# ProPrj_X-Link_V9_3_M_2024-10-04.net
KiCad netlist of a schematic drawn in EasyEDA Pro
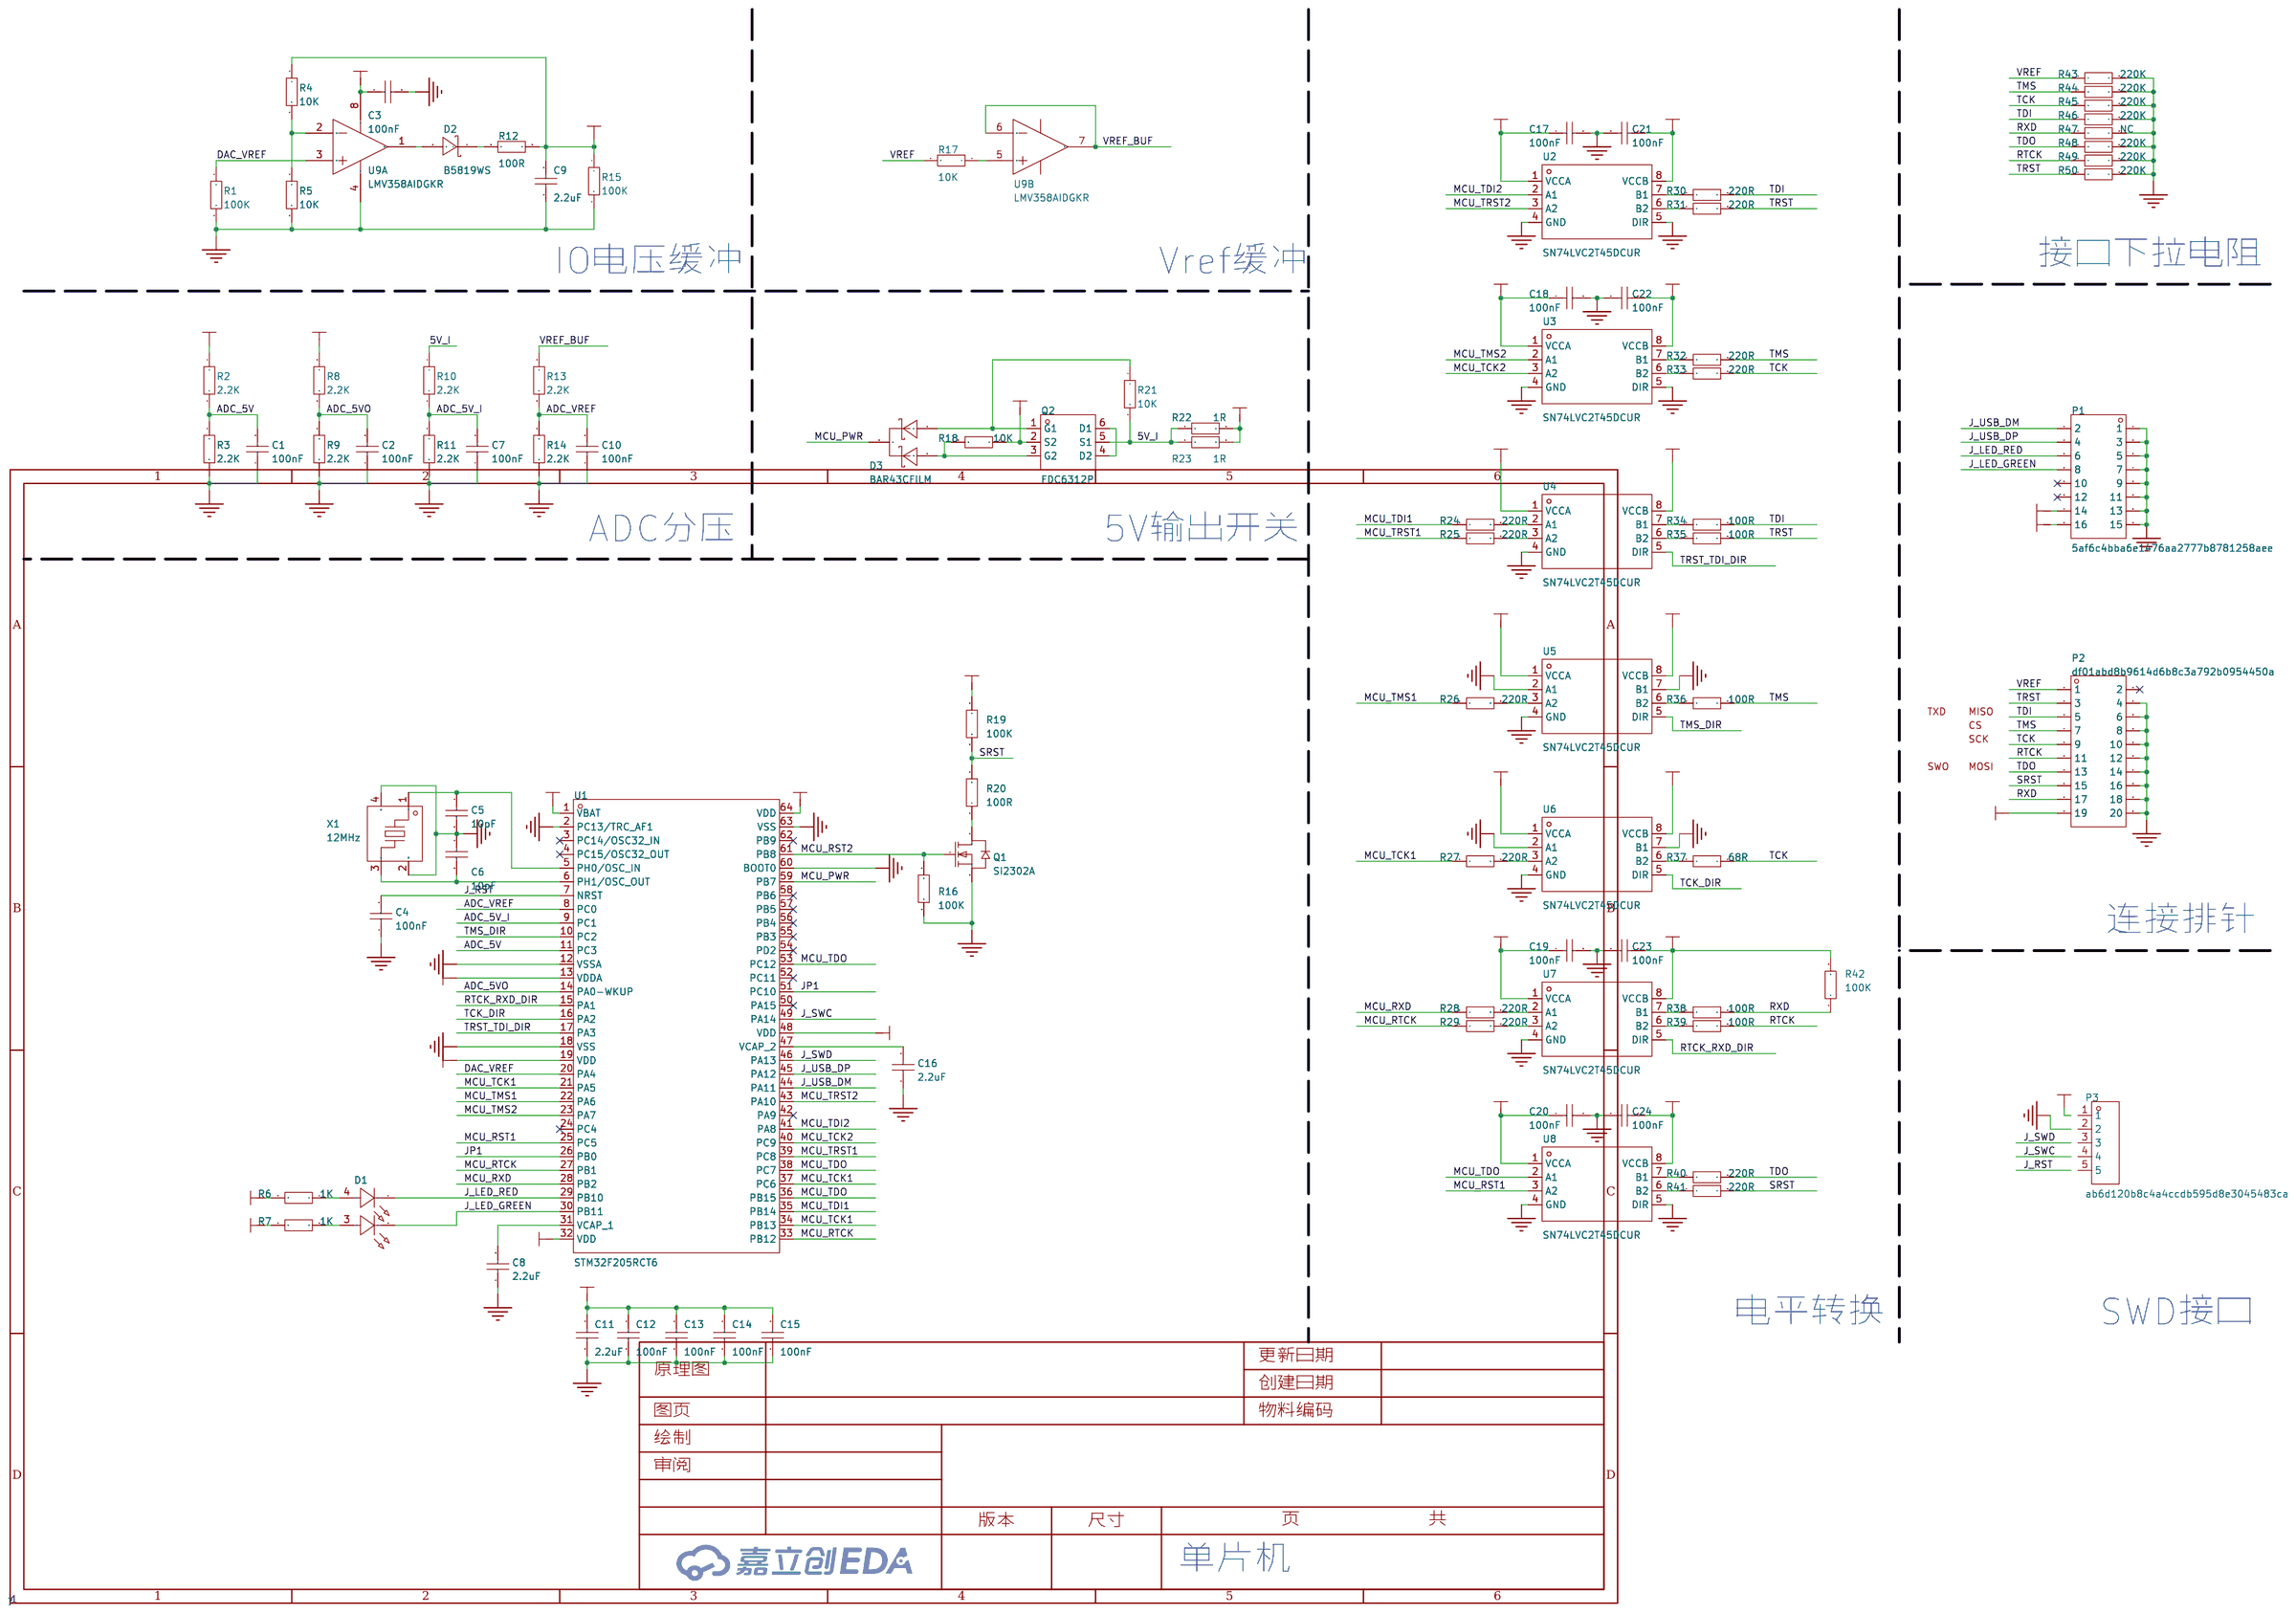
[diagram p0: schematic sheet]

(export (version "E")
  (design (tool "Eeschema 10.0.6"))
  (components
    (comp (ref "C1")
      (value "100nF")
      (footprint "easyedapro:C0402")
      (libsource (lib "easyedapro") (part "C0402"))
    )
    (comp (ref "C2")
      (value "100nF")
      (footprint "easyedapro:C0402")
      (libsource (lib "easyedapro") (part "C0402"))
    )
    (comp (ref "C3")
      (value "100nF")
      (footprint "easyedapro:C0402")
      (libsource (lib "easyedapro") (part "C0402"))
    )
    (comp (ref "C4")
      (value "100nF")
      (footprint "easyedapro:C0603")
      (libsource (lib "easyedapro") (part "C0603"))
    )
    (comp (ref "C5")
      (value "10pF")
      (footprint "easyedapro:C0402")
      (libsource (lib "easyedapro") (part "C0402"))
    )
    (comp (ref "C6")
      (value "10pF")
      (footprint "easyedapro:C0402")
      (libsource (lib "easyedapro") (part "C0402"))
    )
    (comp (ref "C7")
      (value "100nF")
      (footprint "easyedapro:C0402")
      (libsource (lib "easyedapro") (part "C0402"))
    )
    (comp (ref "C8")
      (value "2.2uF")
      (footprint "easyedapro:C0603")
      (libsource (lib "easyedapro") (part "C0603"))
    )
    (comp (ref "C9")
      (value "2.2uF")
      (footprint "easyedapro:C0402")
      (libsource (lib "easyedapro") (part "C0402"))
    )
    (comp (ref "C10")
      (value "100nF")
      (footprint "easyedapro:C0402")
      (libsource (lib "easyedapro") (part "C0402"))
    )
    (comp (ref "C11")
      (value "2.2uF")
      (footprint "easyedapro:C0603")
      (libsource (lib "easyedapro") (part "C0603"))
    )
    (comp (ref "C12")
      (value "100nF")
      (footprint "easyedapro:C0603")
      (libsource (lib "easyedapro") (part "C0603"))
    )
    (comp (ref "C13")
      (value "100nF")
      (footprint "easyedapro:C0603")
      (libsource (lib "easyedapro") (part "C0603"))
    )
    (comp (ref "C14")
      (value "100nF")
      (footprint "easyedapro:C0603")
      (libsource (lib "easyedapro") (part "C0603"))
    )
    (comp (ref "C15")
      (value "100nF")
      (footprint "easyedapro:C0603")
      (libsource (lib "easyedapro") (part "C0603"))
    )
    (comp (ref "C16")
      (value "2.2uF")
      (footprint "easyedapro:C0603")
      (libsource (lib "easyedapro") (part "C0603"))
    )
    (comp (ref "C17")
      (value "100nF")
      (footprint "easyedapro:C0603")
      (libsource (lib "easyedapro") (part "C0603"))
    )
    (comp (ref "C18")
      (value "100nF")
      (footprint "easyedapro:C0603")
      (libsource (lib "easyedapro") (part "C0603"))
    )
    (comp (ref "C19")
      (value "100nF")
      (footprint "easyedapro:C0603")
      (libsource (lib "easyedapro") (part "C0603"))
    )
    (comp (ref "C20")
      (value "100nF")
      (footprint "easyedapro:C0603")
      (libsource (lib "easyedapro") (part "C0603"))
    )
    (comp (ref "C21")
      (value "100nF")
      (footprint "easyedapro:C0603")
      (libsource (lib "easyedapro") (part "C0603"))
    )
    (comp (ref "C22")
      (value "100nF")
      (footprint "easyedapro:C0603")
      (libsource (lib "easyedapro") (part "C0603"))
    )
    (comp (ref "C23")
      (value "100nF")
      (footprint "easyedapro:C0603")
      (libsource (lib "easyedapro") (part "C0603"))
    )
    (comp (ref "C24")
      (value "100nF")
      (footprint "easyedapro:C0603")
      (libsource (lib "easyedapro") (part "C0603"))
    )
    (comp (ref "D1")
      (value "~")
      (footprint "easyedapro:LED1615")
      (libsource (lib "easyedapro") (part "LED1615"))
    )
    (comp (ref "D2")
      (value "B5819WS")
      (footprint "easyedapro:SOD-323_L1.8-W1.3-LS2.5-RD")
      (description "正向压降(Vf):600mV@1A;直流反向耐压(Vr):40V;平均整流电流(Io):1A;")
      (fields (field (name "Manufacturer") "CJ(江苏长电/长晶)"))
      (libsource (lib "easyedapro") (part "B5819WS_C22624"))
    )
    (comp (ref "D3")
      (value "BAR43CFILM")
      (footprint "easyedapro:SOT-23-3_L2.9-W1.3-P1.90-LS2.4-BR")
      (description "二极管配置:1对共阴极;正向压降(Vf):1V@100mA;直流反向耐压(Vr):30V;平均整流电流(Io):100mA;")
      (fields (field (name "Manufacturer") "ST(意法半导体)"))
      (libsource (lib "easyedapro") (part "BAR43CFILM"))
    )
    (comp (ref "P1")
      (value "5af6c4bba6e1476aa2777b8781258aee")
      (footprint "easyedapro:HDR-TH_16P-P1.27-V-M-R2-C8-S1.27-1")
      (libsource (lib "easyedapro") (part "HDR2x8_1.27"))
    )
    (comp (ref "P2")
      (value "df01abd8b9614d6b8c3a792b0954450a")
      (footprint "easyedapro:HDR-TH_20P-P1.27-V-M-R2-C10-S1.27")
      (libsource (lib "easyedapro") (part "HDR2x10_1.27"))
    )
    (comp (ref "P3")
      (value "ab6d120b8c4a4ccdb595d8e3045483ca")
      (footprint "easyedapro:HDR-TH_5P-P1.27-V-M")
      (libsource (lib "easyedapro") (part "HDR1x5_1.27"))
    )
    (comp (ref "Q1")
      (value "SI2302A")
      (footprint "easyedapro:SOT-23-3_L2.9-W1.3-P1.90-LS2.4-BR")
      (fields (field (name "Manufacturer") "UMW(友台半导体)"))
      (libsource (lib "easyedapro") (part "SI2302A"))
    )
    (comp (ref "Q2")
      (value "FDC6312P")
      (footprint "easyedapro:SOT-23-6_L2.9-W1.6-P0.95-LS2.8-BR")
      (description "类型:-;漏源电压(Vdss):-;连续漏极电流(Id):-;功率(Pd):-;导通电阻(RDS(on)@Vgs,Id):-;阈值电压(Vgs(th)@Id):-;")
      (fields (field (name "Manufacturer") "onsemi(安森美)"))
      (libsource (lib "easyedapro") (part "FDC6312P_C241767"))
    )
    (comp (ref "R1")
      (value "100K")
      (footprint "easyedapro:R0402")
      (libsource (lib "easyedapro") (part "R0402"))
    )
    (comp (ref "R2")
      (value "2.2K")
      (footprint "easyedapro:R0402")
      (libsource (lib "easyedapro") (part "R0402"))
    )
    (comp (ref "R3")
      (value "2.2K")
      (footprint "easyedapro:R0402")
      (libsource (lib "easyedapro") (part "R0402"))
    )
    (comp (ref "R4")
      (value "10K")
      (footprint "easyedapro:R0402")
      (libsource (lib "easyedapro") (part "R0402"))
    )
    (comp (ref "R5")
      (value "10K")
      (footprint "easyedapro:R0402")
      (libsource (lib "easyedapro") (part "R0402"))
    )
    (comp (ref "R6") (value "1K") (footprint "easyedapro:R0603") (libsource (lib "easyedapro") (part "电阻")))
    (comp (ref "R7") (value "1K") (footprint "easyedapro:R0603") (libsource (lib "easyedapro") (part "电阻")))
    (comp (ref "R8")
      (value "2.2K")
      (footprint "easyedapro:R0402")
      (libsource (lib "easyedapro") (part "R0402"))
    )
    (comp (ref "R9")
      (value "2.2K")
      (footprint "easyedapro:R0402")
      (libsource (lib "easyedapro") (part "R0402"))
    )
    (comp (ref "R10")
      (value "2.2K")
      (footprint "easyedapro:R0402")
      (libsource (lib "easyedapro") (part "R0402"))
    )
    (comp (ref "R11")
      (value "2.2K")
      (footprint "easyedapro:R0402")
      (libsource (lib "easyedapro") (part "R0402"))
    )
    (comp (ref "R12")
      (value "100R")
      (footprint "easyedapro:R0402")
      (libsource (lib "easyedapro") (part "R0402"))
    )
    (comp (ref "R13")
      (value "2.2K")
      (footprint "easyedapro:R0402")
      (libsource (lib "easyedapro") (part "R0402"))
    )
    (comp (ref "R14")
      (value "2.2K")
      (footprint "easyedapro:R0402")
      (libsource (lib "easyedapro") (part "R0402"))
    )
    (comp (ref "R15")
      (value "100K")
      (footprint "easyedapro:R0402")
      (libsource (lib "easyedapro") (part "R0402"))
    )
    (comp (ref "R16")
      (value "100K")
      (footprint "easyedapro:R0603")
      (libsource (lib "easyedapro") (part "电阻"))
    )
    (comp (ref "R17")
      (value "10K")
      (footprint "easyedapro:R0402")
      (libsource (lib "easyedapro") (part "R0402"))
    )
    (comp (ref "R18") (value "10K") (footprint "easyedapro:R0603") (libsource (lib "easyedapro") (part "电阻")))
    (comp (ref "R19")
      (value "100K")
      (footprint "easyedapro:R0603")
      (libsource (lib "easyedapro") (part "电阻"))
    )
    (comp (ref "R20")
      (value "100R")
      (footprint "easyedapro:R0603")
      (libsource (lib "easyedapro") (part "电阻"))
    )
    (comp (ref "R21") (value "10K") (footprint "easyedapro:R0603") (libsource (lib "easyedapro") (part "电阻")))
    (comp (ref "R22")
      (value "1R")
      (footprint "easyedapro:R0805")
      (libsource (lib "easyedapro") (part "R0805"))
    )
    (comp (ref "R23")
      (value "1R")
      (footprint "easyedapro:R0805")
      (libsource (lib "easyedapro") (part "R0805"))
    )
    (comp (ref "R24")
      (value "220R")
      (footprint "easyedapro:R0603")
      (libsource (lib "easyedapro") (part "电阻"))
    )
    (comp (ref "R25")
      (value "220R")
      (footprint "easyedapro:R0603")
      (libsource (lib "easyedapro") (part "电阻"))
    )
    (comp (ref "R26")
      (value "220R")
      (footprint "easyedapro:R0603")
      (libsource (lib "easyedapro") (part "电阻"))
    )
    (comp (ref "R27")
      (value "220R")
      (footprint "easyedapro:R0603")
      (libsource (lib "easyedapro") (part "电阻"))
    )
    (comp (ref "R28")
      (value "220R")
      (footprint "easyedapro:R0603")
      (libsource (lib "easyedapro") (part "电阻"))
    )
    (comp (ref "R29")
      (value "220R")
      (footprint "easyedapro:R0603")
      (libsource (lib "easyedapro") (part "电阻"))
    )
    (comp (ref "R30")
      (value "220R")
      (footprint "easyedapro:R0603")
      (libsource (lib "easyedapro") (part "电阻"))
    )
    (comp (ref "R31")
      (value "220R")
      (footprint "easyedapro:R0603")
      (libsource (lib "easyedapro") (part "电阻"))
    )
    (comp (ref "R32")
      (value "220R")
      (footprint "easyedapro:R0603")
      (libsource (lib "easyedapro") (part "电阻"))
    )
    (comp (ref "R33")
      (value "220R")
      (footprint "easyedapro:R0603")
      (libsource (lib "easyedapro") (part "电阻"))
    )
    (comp (ref "R34")
      (value "100R")
      (footprint "easyedapro:R0603")
      (libsource (lib "easyedapro") (part "电阻"))
    )
    (comp (ref "R35")
      (value "100R")
      (footprint "easyedapro:R0603")
      (libsource (lib "easyedapro") (part "电阻"))
    )
    (comp (ref "R36")
      (value "100R")
      (footprint "easyedapro:R0603")
      (libsource (lib "easyedapro") (part "电阻"))
    )
    (comp (ref "R37") (value "68R") (footprint "easyedapro:R0603") (libsource (lib "easyedapro") (part "电阻")))
    (comp (ref "R38")
      (value "100R")
      (footprint "easyedapro:R0603")
      (libsource (lib "easyedapro") (part "电阻"))
    )
    (comp (ref "R39")
      (value "100R")
      (footprint "easyedapro:R0603")
      (libsource (lib "easyedapro") (part "电阻"))
    )
    (comp (ref "R40")
      (value "220R")
      (footprint "easyedapro:R0603")
      (libsource (lib "easyedapro") (part "电阻"))
    )
    (comp (ref "R41")
      (value "220R")
      (footprint "easyedapro:R0603")
      (libsource (lib "easyedapro") (part "电阻"))
    )
    (comp (ref "R42")
      (value "100K")
      (footprint "easyedapro:R0603")
      (libsource (lib "easyedapro") (part "电阻"))
    )
    (comp (ref "R43")
      (value "220K")
      (footprint "easyedapro:R0603")
      (libsource (lib "easyedapro") (part "电阻"))
    )
    (comp (ref "R44")
      (value "220K")
      (footprint "easyedapro:R0603")
      (libsource (lib "easyedapro") (part "电阻"))
    )
    (comp (ref "R45")
      (value "220K")
      (footprint "easyedapro:R0603")
      (libsource (lib "easyedapro") (part "电阻"))
    )
    (comp (ref "R46")
      (value "220K")
      (footprint "easyedapro:R0603")
      (libsource (lib "easyedapro") (part "电阻"))
    )
    (comp (ref "R47") (value "NC") (footprint "easyedapro:R0603") (libsource (lib "easyedapro") (part "电阻")))
    (comp (ref "R48")
      (value "220K")
      (footprint "easyedapro:R0603")
      (libsource (lib "easyedapro") (part "电阻"))
    )
    (comp (ref "R49")
      (value "220K")
      (footprint "easyedapro:R0603")
      (libsource (lib "easyedapro") (part "电阻"))
    )
    (comp (ref "R50")
      (value "220K")
      (footprint "easyedapro:R0603")
      (libsource (lib "easyedapro") (part "电阻"))
    )
    (comp (ref "U1")
      (value "STM32F205RCT6")
      (footprint "easyedapro:LQFP-64_L10.0-W10.0-P0.50-LS12.0-BL")
      (description "CPU内核:CM3;程序存储容量:256KB;GPIO端口数量:51;工作电压范围:1.8V~3.6V;CPU最大主频:120MHz;")
      (fields (field (name "Manufacturer") "ST(意法半导体)"))
      (libsource (lib "easyedapro") (part "STM32F205RCT6"))
    )
    (comp (ref "U2")
      (value "SN74LVC2T45DCUR")
      (footprint "easyedapro:VSSOP-8_L2.4-W2.1-P0.50-LS3.2-BR")
      (description "SN74LVC2T45 具有可配置电压转换和三态输出的 2 位双电源总线收发器")
      (fields (field (name "Manufacturer") "TI(德州仪器)"))
      (libsource (lib "easyedapro") (part "SN74LVC2T45DCUR"))
    )
    (comp (ref "U3")
      (value "SN74LVC2T45DCUR")
      (footprint "easyedapro:VSSOP-8_L2.4-W2.1-P0.50-LS3.2-BR")
      (description "SN74LVC2T45 具有可配置电压转换和三态输出的 2 位双电源总线收发器")
      (fields (field (name "Manufacturer") "TI(德州仪器)"))
      (libsource (lib "easyedapro") (part "SN74LVC2T45DCUR"))
    )
    (comp (ref "U4")
      (value "SN74LVC2T45DCUR")
      (footprint "easyedapro:VSSOP-8_L2.4-W2.1-P0.50-LS3.2-BR")
      (description "SN74LVC2T45 具有可配置电压转换和三态输出的 2 位双电源总线收发器")
      (fields (field (name "Manufacturer") "TI(德州仪器)"))
      (libsource (lib "easyedapro") (part "SN74LVC2T45DCUR"))
    )
    (comp (ref "U5")
      (value "SN74LVC2T45DCUR")
      (footprint "easyedapro:VSSOP-8_L2.4-W2.1-P0.50-LS3.2-BR")
      (description "SN74LVC2T45 具有可配置电压转换和三态输出的 2 位双电源总线收发器")
      (fields (field (name "Manufacturer") "TI(德州仪器)"))
      (libsource (lib "easyedapro") (part "SN74LVC2T45DCUR"))
    )
    (comp (ref "U6")
      (value "SN74LVC2T45DCUR")
      (footprint "easyedapro:VSSOP-8_L2.4-W2.1-P0.50-LS3.2-BR")
      (description "SN74LVC2T45 具有可配置电压转换和三态输出的 2 位双电源总线收发器")
      (fields (field (name "Manufacturer") "TI(德州仪器)"))
      (libsource (lib "easyedapro") (part "SN74LVC2T45DCUR"))
    )
    (comp (ref "U7")
      (value "SN74LVC2T45DCUR")
      (footprint "easyedapro:VSSOP-8_L2.4-W2.1-P0.50-LS3.2-BR")
      (description "SN74LVC2T45 具有可配置电压转换和三态输出的 2 位双电源总线收发器")
      (fields (field (name "Manufacturer") "TI(德州仪器)"))
      (libsource (lib "easyedapro") (part "SN74LVC2T45DCUR"))
    )
    (comp (ref "U8")
      (value "SN74LVC2T45DCUR")
      (footprint "easyedapro:VSSOP-8_L2.4-W2.1-P0.50-LS3.2-BR")
      (description "SN74LVC2T45 具有可配置电压转换和三态输出的 2 位双电源总线收发器")
      (fields (field (name "Manufacturer") "TI(德州仪器)"))
      (libsource (lib "easyedapro") (part "SN74LVC2T45DCUR"))
    )
    (comp (ref "U9")
      (value "LMV358AIDGKR")
      (footprint "easyedapro:VSSOP-8_L3.0-W3.0-P0.65-LS5.0-BL")
      (description "放大器数:双路;增益带宽积(GBP):1MHz;输入偏置电流(Ib):10pA;压摆率(SR):1.7V/us;带宽(-3db):-;轨到轨:-;")
      (fields (field (name "Manufacturer") "TI(德州仪器)"))
      (libsource (lib "easyedapro") (part "LMV358AIDGKR"))
    )
    (comp (ref "X1")
      (value "12MHz")
      (footprint "easyedapro:CRYSTAL-SMD_4P-L3.2-W2.5-BL-A")
      (libsource (lib "easyedapro") (part "XTAL3225"))
    )
  )
  (nets
    (net (code "1") (name "/5V_I") (class "Default")
      (node (ref "Q2") (pin "5") (pinfunction "S1_5") (pintype "unspecified"))
      (node (ref "R10") (pin "1") (pinfunction "1_1") (pintype "input"))
      (node (ref "R21") (pin "2") (pinfunction "2_2") (pintype "input"))
      (node (ref "R22") (pin "1") (pinfunction "1_1") (pintype "input"))
      (node (ref "R23") (pin "1") (pinfunction "1_1") (pintype "input"))
    )
    (net (code "2") (name "/ADC_5V") (class "Default")
      (node (ref "C1") (pin "2") (pinfunction "2_2") (pintype "input"))
      (node (ref "R2") (pin "2") (pinfunction "2_2") (pintype "input"))
      (node (ref "R3") (pin "1") (pinfunction "1_1") (pintype "input"))
      (node (ref "U1") (pin "11") (pinfunction "PC3_11") (pintype "unspecified"))
    )
    (net (code "3") (name "/ADC_5VO") (class "Default")
      (node (ref "C2") (pin "2") (pinfunction "2_2") (pintype "input"))
      (node (ref "R8") (pin "2") (pinfunction "2_2") (pintype "input"))
      (node (ref "R9") (pin "1") (pinfunction "1_1") (pintype "input"))
      (node (ref "U1") (pin "14") (pinfunction "PA0-WKUP_14") (pintype "unspecified"))
    )
    (net (code "4") (name "/ADC_5V_I") (class "Default")
      (node (ref "C7") (pin "2") (pinfunction "2_2") (pintype "input"))
      (node (ref "R10") (pin "2") (pinfunction "2_2") (pintype "input"))
      (node (ref "R11") (pin "1") (pinfunction "1_1") (pintype "input"))
      (node (ref "U1") (pin "9") (pinfunction "PC1_9") (pintype "unspecified"))
    )
    (net (code "5") (name "/ADC_VREF") (class "Default")
      (node (ref "C10") (pin "2") (pinfunction "2_2") (pintype "input"))
      (node (ref "R13") (pin "2") (pinfunction "2_2") (pintype "input"))
      (node (ref "R14") (pin "1") (pinfunction "1_1") (pintype "input"))
      (node (ref "U1") (pin "8") (pinfunction "PC0_8") (pintype "unspecified"))
    )
    (net (code "6") (name "/DAC_VREF") (class "Default")
      (node (ref "R1") (pin "1") (pinfunction "1_1") (pintype "input"))
      (node (ref "U1") (pin "20") (pinfunction "PA4_20") (pintype "unspecified"))
      (node (ref "U9") (pin "3") (pinfunction "+INA_3") (pintype "unspecified"))
    )
    (net (code "7") (name "/JP1") (class "Default")
      (node (ref "U1") (pin "26") (pinfunction "PB0_26") (pintype "unspecified"))
      (node (ref "U1") (pin "51") (pinfunction "PC10_51") (pintype "unspecified"))
    )
    (net (code "8") (name "/J_LED_GREEN") (class "Default")
      (node (ref "D1") (pin "2") (pinfunction "K_2") (pintype "unspecified"))
      (node (ref "P1") (pin "8") (pinfunction "8_8") (pintype "unspecified"))
      (node (ref "U1") (pin "30") (pinfunction "PB11_30") (pintype "unspecified"))
    )
    (net (code "9") (name "/J_LED_RED") (class "Default")
      (node (ref "D1") (pin "1") (pinfunction "K_1") (pintype "unspecified"))
      (node (ref "P1") (pin "6") (pinfunction "6_6") (pintype "unspecified"))
      (node (ref "U1") (pin "29") (pinfunction "PB10_29") (pintype "unspecified"))
    )
    (net (code "10") (name "/J_RST") (class "Default")
      (node (ref "C4") (pin "2") (pinfunction "2_2") (pintype "input"))
      (node (ref "U1") (pin "7") (pinfunction "NRST_7") (pintype "unspecified"))
    )
    (net (code "11") (name "/J_SWC") (class "Default")
      (node (ref "U1") (pin "49") (pinfunction "PA14_49") (pintype "unspecified"))
    )
    (net (code "12") (name "/J_SWD") (class "Default")
      (node (ref "U1") (pin "46") (pinfunction "PA13_46") (pintype "unspecified"))
    )
    (net (code "13") (name "/J_USB_DM") (class "Default")
      (node (ref "P1") (pin "2") (pinfunction "2_2") (pintype "unspecified"))
      (node (ref "U1") (pin "44") (pinfunction "PA11_44") (pintype "unspecified"))
    )
    (net (code "14") (name "/J_USB_DP") (class "Default")
      (node (ref "P1") (pin "4") (pinfunction "4_4") (pintype "unspecified"))
      (node (ref "U1") (pin "45") (pinfunction "PA12_45") (pintype "unspecified"))
    )
    (net (code "15") (name "/MCU_PWR") (class "Default")
      (node (ref "D3") (pin "3") (pinfunction "K_3") (pintype "unspecified"))
      (node (ref "U1") (pin "59") (pinfunction "PB7_59") (pintype "unspecified"))
    )
    (net (code "16") (name "/MCU_RST1") (class "Default")
      (node (ref "U1") (pin "25") (pinfunction "PC5_25") (pintype "unspecified"))
      (node (ref "U8") (pin "3") (pinfunction "A2_3") (pintype "unspecified"))
    )
    (net (code "17") (name "/MCU_RST2") (class "Default")
      (node (ref "Q1") (pin "1") (pinfunction "G_1") (pintype "unspecified"))
      (node (ref "R16") (pin "1") (pinfunction "1_1") (pintype "input"))
      (node (ref "U1") (pin "61") (pinfunction "PB8_61") (pintype "unspecified"))
    )
    (net (code "18") (name "/MCU_RTCK") (class "Default")
      (node (ref "R29") (pin "1") (pinfunction "1_1") (pintype "input"))
      (node (ref "U1") (pin "27") (pinfunction "PB1_27") (pintype "unspecified"))
      (node (ref "U1") (pin "33") (pinfunction "PB12_33") (pintype "unspecified"))
    )
    (net (code "19") (name "/MCU_RXD") (class "Default")
      (node (ref "R28") (pin "1") (pinfunction "1_1") (pintype "input"))
      (node (ref "U1") (pin "28") (pinfunction "PB2_28") (pintype "unspecified"))
    )
    (net (code "20") (name "/MCU_TCK1") (class "Default")
      (node (ref "R27") (pin "1") (pinfunction "1_1") (pintype "input"))
      (node (ref "U1") (pin "21") (pinfunction "PA5_21") (pintype "unspecified"))
      (node (ref "U1") (pin "34") (pinfunction "PB13_34") (pintype "unspecified"))
      (node (ref "U1") (pin "37") (pinfunction "PC6_37") (pintype "unspecified"))
    )
    (net (code "21") (name "/MCU_TCK2") (class "Default")
      (node (ref "U1") (pin "40") (pinfunction "PC9_40") (pintype "unspecified"))
      (node (ref "U3") (pin "3") (pinfunction "A2_3") (pintype "unspecified"))
    )
    (net (code "22") (name "/MCU_TDI1") (class "Default")
      (node (ref "R24") (pin "1") (pinfunction "1_1") (pintype "input"))
      (node (ref "U1") (pin "35") (pinfunction "PB14_35") (pintype "unspecified"))
    )
    (net (code "23") (name "/MCU_TDI2") (class "Default")
      (node (ref "U1") (pin "41") (pinfunction "PA8_41") (pintype "unspecified"))
      (node (ref "U2") (pin "2") (pinfunction "A1_2") (pintype "unspecified"))
    )
    (net (code "24") (name "/MCU_TDO") (class "Default")
      (node (ref "U1") (pin "36") (pinfunction "PB15_36") (pintype "unspecified"))
      (node (ref "U1") (pin "38") (pinfunction "PC7_38") (pintype "unspecified"))
      (node (ref "U1") (pin "53") (pinfunction "PC12_53") (pintype "unspecified"))
      (node (ref "U8") (pin "2") (pinfunction "A1_2") (pintype "unspecified"))
    )
    (net (code "25") (name "/MCU_TMS1") (class "Default")
      (node (ref "R26") (pin "1") (pinfunction "1_1") (pintype "input"))
      (node (ref "U1") (pin "22") (pinfunction "PA6_22") (pintype "unspecified"))
    )
    (net (code "26") (name "/MCU_TMS2") (class "Default")
      (node (ref "U1") (pin "23") (pinfunction "PA7_23") (pintype "unspecified"))
      (node (ref "U3") (pin "2") (pinfunction "A1_2") (pintype "unspecified"))
    )
    (net (code "27") (name "/MCU_TRST1") (class "Default")
      (node (ref "R25") (pin "1") (pinfunction "1_1") (pintype "input"))
      (node (ref "U1") (pin "39") (pinfunction "PC8_39") (pintype "unspecified"))
    )
    (net (code "28") (name "/MCU_TRST2") (class "Default")
      (node (ref "U1") (pin "43") (pinfunction "PA10_43") (pintype "unspecified"))
      (node (ref "U2") (pin "3") (pinfunction "A2_3") (pintype "unspecified"))
    )
    (net (code "29") (name "/RTCK") (class "Default")
      (node (ref "P2") (pin "11") (pinfunction "11_11") (pintype "unspecified"))
      (node (ref "R39") (pin "2") (pinfunction "2_2") (pintype "input"))
      (node (ref "R49") (pin "1") (pinfunction "1_1") (pintype "input"))
    )
    (net (code "30") (name "/RTCK_RXD_DIR") (class "Default")
      (node (ref "U1") (pin "15") (pinfunction "PA1_15") (pintype "unspecified"))
      (node (ref "U7") (pin "5") (pinfunction "DIR_5") (pintype "unspecified"))
    )
    (net (code "31") (name "/RXD") (class "Default")
      (node (ref "P2") (pin "17") (pinfunction "17_17") (pintype "unspecified"))
      (node (ref "R38") (pin "2") (pinfunction "2_2") (pintype "input"))
      (node (ref "R42") (pin "1") (pinfunction "1_1") (pintype "input"))
      (node (ref "R47") (pin "1") (pinfunction "1_1") (pintype "input"))
    )
    (net (code "32") (name "/SRST") (class "Default")
      (node (ref "P2") (pin "15") (pinfunction "15_15") (pintype "unspecified"))
      (node (ref "R19") (pin "2") (pinfunction "2_2") (pintype "input"))
      (node (ref "R20") (pin "2") (pinfunction "2_2") (pintype "input"))
      (node (ref "R41") (pin "2") (pinfunction "2_2") (pintype "input"))
    )
    (net (code "33") (name "/TCK") (class "Default")
      (node (ref "P2") (pin "9") (pinfunction "9_9") (pintype "unspecified"))
      (node (ref "R33") (pin "2") (pinfunction "2_2") (pintype "input"))
      (node (ref "R37") (pin "2") (pinfunction "2_2") (pintype "input"))
      (node (ref "R45") (pin "1") (pinfunction "1_1") (pintype "input"))
    )
    (net (code "34") (name "/TCK_DIR") (class "Default")
      (node (ref "U1") (pin "16") (pinfunction "PA2_16") (pintype "unspecified"))
      (node (ref "U6") (pin "5") (pinfunction "DIR_5") (pintype "unspecified"))
    )
    (net (code "35") (name "/TDI") (class "Default")
      (node (ref "P2") (pin "5") (pinfunction "5_5") (pintype "unspecified"))
      (node (ref "R30") (pin "2") (pinfunction "2_2") (pintype "input"))
      (node (ref "R34") (pin "2") (pinfunction "2_2") (pintype "input"))
      (node (ref "R46") (pin "1") (pinfunction "1_1") (pintype "input"))
    )
    (net (code "36") (name "/TDO") (class "Default")
      (node (ref "P2") (pin "13") (pinfunction "13_13") (pintype "unspecified"))
      (node (ref "R40") (pin "2") (pinfunction "2_2") (pintype "input"))
      (node (ref "R48") (pin "1") (pinfunction "1_1") (pintype "input"))
    )
    (net (code "37") (name "/TMS") (class "Default")
      (node (ref "P2") (pin "7") (pinfunction "7_7") (pintype "unspecified"))
      (node (ref "R32") (pin "2") (pinfunction "2_2") (pintype "input"))
      (node (ref "R36") (pin "2") (pinfunction "2_2") (pintype "input"))
      (node (ref "R44") (pin "1") (pinfunction "1_1") (pintype "input"))
    )
    (net (code "38") (name "/TMS_DIR") (class "Default")
      (node (ref "U1") (pin "10") (pinfunction "PC2_10") (pintype "unspecified"))
      (node (ref "U5") (pin "5") (pinfunction "DIR_5") (pintype "unspecified"))
    )
    (net (code "39") (name "/TRST") (class "Default")
      (node (ref "P2") (pin "3") (pinfunction "3_3") (pintype "unspecified"))
      (node (ref "R31") (pin "2") (pinfunction "2_2") (pintype "input"))
      (node (ref "R35") (pin "2") (pinfunction "2_2") (pintype "input"))
      (node (ref "R50") (pin "1") (pinfunction "1_1") (pintype "input"))
    )
    (net (code "40") (name "/TRST_TDI_DIR") (class "Default")
      (node (ref "U1") (pin "17") (pinfunction "PA3_17") (pintype "unspecified"))
      (node (ref "U4") (pin "5") (pinfunction "DIR_5") (pintype "unspecified"))
    )
    (net (code "41") (name "/VREF") (class "Default")
      (node (ref "P2") (pin "1") (pinfunction "1_1") (pintype "unspecified"))
      (node (ref "R17") (pin "2") (pinfunction "2_2") (pintype "input"))
      (node (ref "R43") (pin "1") (pinfunction "1_1") (pintype "input"))
    )
    (net (code "42") (name "/VREF_BUF") (class "Default")
      (node (ref "R13") (pin "1") (pinfunction "1_1") (pintype "input"))
      (node (ref "U9") (pin "6") (pinfunction "-INB_6") (pintype "unspecified"))
      (node (ref "U9") (pin "7") (pinfunction "OUTB_7") (pintype "output"))
    )
    (net (code "43") (name "3.3V") (class "Default")
      (node (ref "C11") (pin "2") (pinfunction "2_2") (pintype "input"))
      (node (ref "C12") (pin "2") (pinfunction "2_2") (pintype "input"))
      (node (ref "C13") (pin "2") (pinfunction "2_2") (pintype "input"))
      (node (ref "C14") (pin "2") (pinfunction "2_2") (pintype "input"))
      (node (ref "C15") (pin "2") (pinfunction "2_2") (pintype "input"))
      (node (ref "C17") (pin "1") (pinfunction "1_1") (pintype "input"))
      (node (ref "C18") (pin "1") (pinfunction "1_1") (pintype "input"))
      (node (ref "C19") (pin "1") (pinfunction "1_1") (pintype "input"))
      (node (ref "C20") (pin "1") (pinfunction "1_1") (pintype "input"))
      (node (ref "P1") (pin "14") (pinfunction "14_14") (pintype "unspecified"))
      (node (ref "R6") (pin "2") (pinfunction "2_2") (pintype "input"))
      (node (ref "R7") (pin "2") (pinfunction "2_2") (pintype "input"))
      (node (ref "U1") (pin "1") (pinfunction "VBAT_1") (pintype "unspecified"))
      (node (ref "U1") (pin "13") (pinfunction "VDDA_13") (pintype "unspecified"))
      (node (ref "U1") (pin "19") (pinfunction "VDD_19") (pintype "unspecified"))
      (node (ref "U1") (pin "32") (pinfunction "VDD_32") (pintype "unspecified"))
      (node (ref "U1") (pin "48") (pinfunction "VDD_48") (pintype "unspecified"))
      (node (ref "U1") (pin "64") (pinfunction "VDD_64") (pintype "unspecified"))
      (node (ref "U2") (pin "1") (pinfunction "VCCA_1") (pintype "unspecified"))
      (node (ref "U3") (pin "1") (pinfunction "VCCA_1") (pintype "unspecified"))
      (node (ref "U4") (pin "1") (pinfunction "VCCA_1") (pintype "unspecified"))
      (node (ref "U5") (pin "1") (pinfunction "VCCA_1") (pintype "unspecified"))
      (node (ref "U6") (pin "1") (pinfunction "VCCA_1") (pintype "unspecified"))
      (node (ref "U7") (pin "1") (pinfunction "VCCA_1") (pintype "unspecified"))
      (node (ref "U8") (pin "1") (pinfunction "VCCA_1") (pintype "unspecified"))
    )
    (net (code "44") (name "5V") (class "Default")
      (node (ref "C3") (pin "1") (pinfunction "1_1") (pintype "input"))
      (node (ref "P1") (pin "16") (pinfunction "16_16") (pintype "unspecified"))
      (node (ref "R2") (pin "1") (pinfunction "1_1") (pintype "input"))
      (node (ref "R22") (pin "2") (pinfunction "2_2") (pintype "input"))
      (node (ref "R23") (pin "2") (pinfunction "2_2") (pintype "input"))
      (node (ref "U9") (pin "8") (pinfunction "V+_8") (pintype "unspecified"))
    )
    (net (code "45") (name "5V_OUT") (class "Default")
      (node (ref "P2") (pin "19") (pinfunction "19_19") (pintype "unspecified"))
      (node (ref "Q2") (pin "2") (pinfunction "S2_2") (pintype "unspecified"))
      (node (ref "R18") (pin "1") (pinfunction "1_1") (pintype "input"))
      (node (ref "R8") (pin "1") (pinfunction "1_1") (pintype "input"))
    )
    (net (code "46") (name "GND") (class "Default")
      (node (ref "C1") (pin "1") (pinfunction "1_1") (pintype "input"))
      (node (ref "C10") (pin "1") (pinfunction "1_1") (pintype "input"))
      (node (ref "C11") (pin "1") (pinfunction "1_1") (pintype "input"))
      (node (ref "C12") (pin "1") (pinfunction "1_1") (pintype "input"))
      (node (ref "C13") (pin "1") (pinfunction "1_1") (pintype "input"))
      (node (ref "C14") (pin "1") (pinfunction "1_1") (pintype "input"))
      (node (ref "C15") (pin "1") (pinfunction "1_1") (pintype "input"))
      (node (ref "C16") (pin "1") (pinfunction "1_1") (pintype "input"))
      (node (ref "C17") (pin "2") (pinfunction "2_2") (pintype "input"))
      (node (ref "C18") (pin "2") (pinfunction "2_2") (pintype "input"))
      (node (ref "C19") (pin "2") (pinfunction "2_2") (pintype "input"))
      (node (ref "C2") (pin "1") (pinfunction "1_1") (pintype "input"))
      (node (ref "C20") (pin "2") (pinfunction "2_2") (pintype "input"))
      (node (ref "C21") (pin "1") (pinfunction "1_1") (pintype "input"))
      (node (ref "C22") (pin "1") (pinfunction "1_1") (pintype "input"))
      (node (ref "C23") (pin "1") (pinfunction "1_1") (pintype "input"))
      (node (ref "C24") (pin "1") (pinfunction "1_1") (pintype "input"))
      (node (ref "C3") (pin "2") (pinfunction "2_2") (pintype "input"))
      (node (ref "C4") (pin "1") (pinfunction "1_1") (pintype "input"))
      (node (ref "C5") (pin "2") (pinfunction "2_2") (pintype "input"))
      (node (ref "C6") (pin "1") (pinfunction "1_1") (pintype "input"))
      (node (ref "C7") (pin "1") (pinfunction "1_1") (pintype "input"))
      (node (ref "C8") (pin "1") (pinfunction "1_1") (pintype "input"))
      (node (ref "C9") (pin "1") (pinfunction "1_1") (pintype "input"))
      (node (ref "P1") (pin "1") (pinfunction "1_1") (pintype "unspecified"))
      (node (ref "P1") (pin "11") (pinfunction "11_11") (pintype "unspecified"))
      (node (ref "P1") (pin "13") (pinfunction "13_13") (pintype "unspecified"))
      (node (ref "P1") (pin "15") (pinfunction "15_15") (pintype "unspecified"))
      (node (ref "P1") (pin "3") (pinfunction "3_3") (pintype "unspecified"))
      (node (ref "P1") (pin "5") (pinfunction "5_5") (pintype "unspecified"))
      (node (ref "P1") (pin "7") (pinfunction "7_7") (pintype "unspecified"))
      (node (ref "P1") (pin "9") (pinfunction "9_9") (pintype "unspecified"))
      (node (ref "P2") (pin "10") (pinfunction "10_10") (pintype "unspecified"))
      (node (ref "P2") (pin "12") (pinfunction "12_12") (pintype "unspecified"))
      (node (ref "P2") (pin "14") (pinfunction "14_14") (pintype "unspecified"))
      (node (ref "P2") (pin "16") (pinfunction "16_16") (pintype "unspecified"))
      (node (ref "P2") (pin "18") (pinfunction "18_18") (pintype "unspecified"))
      (node (ref "P2") (pin "20") (pinfunction "20_20") (pintype "unspecified"))
      (node (ref "P2") (pin "4") (pinfunction "4_4") (pintype "unspecified"))
      (node (ref "P2") (pin "6") (pinfunction "6_6") (pintype "unspecified"))
      (node (ref "P2") (pin "8") (pinfunction "8_8") (pintype "unspecified"))
      (node (ref "Q1") (pin "2") (pinfunction "S_2") (pintype "unspecified"))
      (node (ref "R1") (pin "2") (pinfunction "2_2") (pintype "input"))
      (node (ref "R11") (pin "2") (pinfunction "2_2") (pintype "input"))
      (node (ref "R14") (pin "2") (pinfunction "2_2") (pintype "input"))
      (node (ref "R15") (pin "2") (pinfunction "2_2") (pintype "input"))
      (node (ref "R16") (pin "2") (pinfunction "2_2") (pintype "input"))
      (node (ref "R3") (pin "2") (pinfunction "2_2") (pintype "input"))
      (node (ref "R43") (pin "2") (pinfunction "2_2") (pintype "input"))
      (node (ref "R44") (pin "2") (pinfunction "2_2") (pintype "input"))
      (node (ref "R45") (pin "2") (pinfunction "2_2") (pintype "input"))
      (node (ref "R46") (pin "2") (pinfunction "2_2") (pintype "input"))
      (node (ref "R47") (pin "2") (pinfunction "2_2") (pintype "input"))
      (node (ref "R48") (pin "2") (pinfunction "2_2") (pintype "input"))
      (node (ref "R49") (pin "2") (pinfunction "2_2") (pintype "input"))
      (node (ref "R5") (pin "2") (pinfunction "2_2") (pintype "input"))
      (node (ref "R50") (pin "2") (pinfunction "2_2") (pintype "input"))
      (node (ref "R9") (pin "2") (pinfunction "2_2") (pintype "input"))
      (node (ref "U1") (pin "12") (pinfunction "VSSA_12") (pintype "unspecified"))
      (node (ref "U1") (pin "18") (pinfunction "VSS_18") (pintype "unspecified"))
      (node (ref "U1") (pin "2") (pinfunction "PC13/TRC_AF1_2") (pintype "unspecified"))
      (node (ref "U1") (pin "60") (pinfunction "BOOT0_60") (pintype "unspecified"))
      (node (ref "U1") (pin "63") (pinfunction "VSS_63") (pintype "unspecified"))
      (node (ref "U2") (pin "4") (pinfunction "GND_4") (pintype "unspecified"))
      (node (ref "U2") (pin "5") (pinfunction "DIR_5") (pintype "unspecified"))
      (node (ref "U3") (pin "4") (pinfunction "GND_4") (pintype "unspecified"))
      (node (ref "U3") (pin "5") (pinfunction "DIR_5") (pintype "unspecified"))
      (node (ref "U4") (pin "4") (pinfunction "GND_4") (pintype "unspecified"))
      (node (ref "U5") (pin "2") (pinfunction "A1_2") (pintype "unspecified"))
      (node (ref "U5") (pin "4") (pinfunction "GND_4") (pintype "unspecified"))
      (node (ref "U5") (pin "7") (pinfunction "B1_7") (pintype "unspecified"))
      (node (ref "U6") (pin "2") (pinfunction "A1_2") (pintype "unspecified"))
      (node (ref "U6") (pin "4") (pinfunction "GND_4") (pintype "unspecified"))
      (node (ref "U6") (pin "7") (pinfunction "B1_7") (pintype "unspecified"))
      (node (ref "U7") (pin "4") (pinfunction "GND_4") (pintype "unspecified"))
      (node (ref "U8") (pin "4") (pinfunction "GND_4") (pintype "unspecified"))
      (node (ref "U8") (pin "5") (pinfunction "DIR_5") (pintype "unspecified"))
      (node (ref "U9") (pin "4") (pinfunction "V-_4") (pintype "unspecified"))
      (node (ref "X1") (pin "2") (pinfunction "GND_2") (pintype "input"))
      (node (ref "X1") (pin "4") (pinfunction "GND_4") (pintype "input"))
    )
    (net (code "47") (name "Net-(D1-A-Pad3)") (class "Default")
      (node (ref "D1") (pin "3") (pinfunction "A_3") (pintype "unspecified"))
      (node (ref "R7") (pin "1") (pinfunction "1_1") (pintype "input"))
    )
    (net (code "48") (name "Net-(D1-A-Pad4)") (class "Default")
      (node (ref "D1") (pin "4") (pinfunction "A_4") (pintype "unspecified"))
      (node (ref "R6") (pin "1") (pinfunction "1_1") (pintype "input"))
    )
    (net (code "49") (name "Net-(D2-A)") (class "Default")
      (node (ref "D2") (pin "2") (pinfunction "A_2") (pintype "unspecified"))
      (node (ref "U9") (pin "1") (pinfunction "OUTA_1") (pintype "output"))
    )
    (net (code "50") (name "Net-(D2-K)") (class "Default")
      (node (ref "D2") (pin "1") (pinfunction "K_1") (pintype "unspecified"))
      (node (ref "R12") (pin "2") (pinfunction "2_2") (pintype "input"))
    )
    (net (code "51") (name "Net-(D3-A1)") (class "Default")
      (node (ref "D3") (pin "1") (pinfunction "A1_1") (pintype "unspecified"))
      (node (ref "Q2") (pin "3") (pinfunction "G2_3") (pintype "unspecified"))
      (node (ref "R18") (pin "2") (pinfunction "2_2") (pintype "input"))
    )
    (net (code "52") (name "Net-(D3-A2)") (class "Default")
      (node (ref "D3") (pin "2") (pinfunction "A2_2") (pintype "unspecified"))
      (node (ref "Q2") (pin "1") (pinfunction "G1_1") (pintype "unspecified"))
      (node (ref "R21") (pin "1") (pinfunction "1_1") (pintype "input"))
    )
    (net (code "53") (name "Net-(Q1-D)") (class "Default")
      (node (ref "Q1") (pin "3") (pinfunction "D_3") (pintype "unspecified"))
      (node (ref "R20") (pin "1") (pinfunction "1_1") (pintype "input"))
    )
    (net (code "54") (name "Net-(Q2-D1)") (class "Default")
      (node (ref "Q2") (pin "4") (pinfunction "D2_4") (pintype "unspecified"))
      (node (ref "Q2") (pin "6") (pinfunction "D1_6") (pintype "unspecified"))
    )
    (net (code "55") (name "Net-(U1-PH0{slash}OSC_IN)") (class "Default")
      (node (ref "C5") (pin "1") (pinfunction "1_1") (pintype "input"))
      (node (ref "U1") (pin "5") (pinfunction "PH0/OSC_IN_5") (pintype "unspecified"))
      (node (ref "X1") (pin "1") (pinfunction "1_1") (pintype "input"))
    )
    (net (code "56") (name "Net-(U1-PH1{slash}OSC_OUT)") (class "Default")
      (node (ref "C6") (pin "2") (pinfunction "2_2") (pintype "input"))
      (node (ref "U1") (pin "6") (pinfunction "PH1/OSC_OUT_6") (pintype "unspecified"))
      (node (ref "X1") (pin "3") (pinfunction "3_3") (pintype "input"))
    )
    (net (code "57") (name "Net-(U1-VCAP_1)") (class "Default")
      (node (ref "C8") (pin "2") (pinfunction "2_2") (pintype "input"))
      (node (ref "U1") (pin "31") (pinfunction "VCAP_1_31") (pintype "unspecified"))
    )
    (net (code "58") (name "Net-(U1-VCAP_2)") (class "Default")
      (node (ref "C16") (pin "2") (pinfunction "2_2") (pintype "input"))
      (node (ref "U1") (pin "47") (pinfunction "VCAP_2_47") (pintype "unspecified"))
    )
    (net (code "59") (name "Net-(U2-B1)") (class "Default")
      (node (ref "R30") (pin "1") (pinfunction "1_1") (pintype "input"))
      (node (ref "U2") (pin "7") (pinfunction "B1_7") (pintype "unspecified"))
    )
    (net (code "60") (name "Net-(U2-B2)") (class "Default")
      (node (ref "R31") (pin "1") (pinfunction "1_1") (pintype "input"))
      (node (ref "U2") (pin "6") (pinfunction "B2_6") (pintype "unspecified"))
    )
    (net (code "61") (name "Net-(U3-B1)") (class "Default")
      (node (ref "R32") (pin "1") (pinfunction "1_1") (pintype "input"))
      (node (ref "U3") (pin "7") (pinfunction "B1_7") (pintype "unspecified"))
    )
    (net (code "62") (name "Net-(U3-B2)") (class "Default")
      (node (ref "R33") (pin "1") (pinfunction "1_1") (pintype "input"))
      (node (ref "U3") (pin "6") (pinfunction "B2_6") (pintype "unspecified"))
    )
    (net (code "63") (name "Net-(U4-A1)") (class "Default")
      (node (ref "R24") (pin "2") (pinfunction "2_2") (pintype "input"))
      (node (ref "U4") (pin "2") (pinfunction "A1_2") (pintype "unspecified"))
    )
    (net (code "64") (name "Net-(U4-A2)") (class "Default")
      (node (ref "R25") (pin "2") (pinfunction "2_2") (pintype "input"))
      (node (ref "U4") (pin "3") (pinfunction "A2_3") (pintype "unspecified"))
    )
    (net (code "65") (name "Net-(U4-B1)") (class "Default")
      (node (ref "R34") (pin "1") (pinfunction "1_1") (pintype "input"))
      (node (ref "U4") (pin "7") (pinfunction "B1_7") (pintype "unspecified"))
    )
    (net (code "66") (name "Net-(U4-B2)") (class "Default")
      (node (ref "R35") (pin "1") (pinfunction "1_1") (pintype "input"))
      (node (ref "U4") (pin "6") (pinfunction "B2_6") (pintype "unspecified"))
    )
    (net (code "67") (name "Net-(U5-A2)") (class "Default")
      (node (ref "R26") (pin "2") (pinfunction "2_2") (pintype "input"))
      (node (ref "U5") (pin "3") (pinfunction "A2_3") (pintype "unspecified"))
    )
    (net (code "68") (name "Net-(U5-B2)") (class "Default")
      (node (ref "R36") (pin "1") (pinfunction "1_1") (pintype "input"))
      (node (ref "U5") (pin "6") (pinfunction "B2_6") (pintype "unspecified"))
    )
    (net (code "69") (name "Net-(U6-A2)") (class "Default")
      (node (ref "R27") (pin "2") (pinfunction "2_2") (pintype "input"))
      (node (ref "U6") (pin "3") (pinfunction "A2_3") (pintype "unspecified"))
    )
    (net (code "70") (name "Net-(U6-B2)") (class "Default")
      (node (ref "R37") (pin "1") (pinfunction "1_1") (pintype "input"))
      (node (ref "U6") (pin "6") (pinfunction "B2_6") (pintype "unspecified"))
    )
    (net (code "71") (name "Net-(U7-A1)") (class "Default")
      (node (ref "R28") (pin "2") (pinfunction "2_2") (pintype "input"))
      (node (ref "U7") (pin "2") (pinfunction "A1_2") (pintype "unspecified"))
    )
    (net (code "72") (name "Net-(U7-A2)") (class "Default")
      (node (ref "R29") (pin "2") (pinfunction "2_2") (pintype "input"))
      (node (ref "U7") (pin "3") (pinfunction "A2_3") (pintype "unspecified"))
    )
    (net (code "73") (name "Net-(U7-B1)") (class "Default")
      (node (ref "R38") (pin "1") (pinfunction "1_1") (pintype "input"))
      (node (ref "U7") (pin "7") (pinfunction "B1_7") (pintype "unspecified"))
    )
    (net (code "74") (name "Net-(U7-B2)") (class "Default")
      (node (ref "R39") (pin "1") (pinfunction "1_1") (pintype "input"))
      (node (ref "U7") (pin "6") (pinfunction "B2_6") (pintype "unspecified"))
    )
    (net (code "75") (name "Net-(U8-B1)") (class "Default")
      (node (ref "R40") (pin "1") (pinfunction "1_1") (pintype "input"))
      (node (ref "U8") (pin "7") (pinfunction "B1_7") (pintype "unspecified"))
    )
    (net (code "76") (name "Net-(U8-B2)") (class "Default")
      (node (ref "R41") (pin "1") (pinfunction "1_1") (pintype "input"))
      (node (ref "U8") (pin "6") (pinfunction "B2_6") (pintype "unspecified"))
    )
    (net (code "77") (name "Net-(U9A--INA)") (class "Default")
      (node (ref "R4") (pin "2") (pinfunction "2_2") (pintype "input"))
      (node (ref "R5") (pin "1") (pinfunction "1_1") (pintype "input"))
      (node (ref "U9") (pin "2") (pinfunction "-INA_2") (pintype "unspecified"))
    )
    (net (code "78") (name "Net-(U9B-+INB)") (class "Default")
      (node (ref "R17") (pin "1") (pinfunction "1_1") (pintype "input"))
      (node (ref "U9") (pin "5") (pinfunction "+INB_5") (pintype "unspecified"))
    )
    (net (code "79") (name "VIO") (class "Default")
      (node (ref "C21") (pin "2") (pinfunction "2_2") (pintype "input"))
      (node (ref "C22") (pin "2") (pinfunction "2_2") (pintype "input"))
      (node (ref "C23") (pin "2") (pinfunction "2_2") (pintype "input"))
      (node (ref "C24") (pin "2") (pinfunction "2_2") (pintype "input"))
      (node (ref "C9") (pin "2") (pinfunction "2_2") (pintype "input"))
      (node (ref "R12") (pin "1") (pinfunction "1_1") (pintype "input"))
      (node (ref "R15") (pin "1") (pinfunction "1_1") (pintype "input"))
      (node (ref "R19") (pin "1") (pinfunction "1_1") (pintype "input"))
      (node (ref "R4") (pin "1") (pinfunction "1_1") (pintype "input"))
      (node (ref "R42") (pin "2") (pinfunction "2_2") (pintype "input"))
      (node (ref "U2") (pin "8") (pinfunction "VCCB_8") (pintype "unspecified"))
      (node (ref "U3") (pin "8") (pinfunction "VCCB_8") (pintype "unspecified"))
      (node (ref "U4") (pin "8") (pinfunction "VCCB_8") (pintype "unspecified"))
      (node (ref "U5") (pin "8") (pinfunction "VCCB_8") (pintype "unspecified"))
      (node (ref "U6") (pin "8") (pinfunction "VCCB_8") (pintype "unspecified"))
      (node (ref "U7") (pin "8") (pinfunction "VCCB_8") (pintype "unspecified"))
      (node (ref "U8") (pin "8") (pinfunction "VCCB_8") (pintype "unspecified"))
    )
    (net (code "80") (name "unconnected-(P1-Pad10)") (class "Default")
      (node (ref "P1") (pin "10") (pinfunction "10_10") (pintype "unspecified+no_connect"))
    )
    (net (code "81") (name "unconnected-(P1-Pad12)") (class "Default")
      (node (ref "P1") (pin "12") (pinfunction "12_12") (pintype "unspecified+no_connect"))
    )
    (net (code "82") (name "unconnected-(P2-Pad2)") (class "Default")
      (node (ref "P2") (pin "2") (pinfunction "2_2") (pintype "unspecified+no_connect"))
    )
    (net (code "83") (name "unconnected-(P3-Pad1)") (class "Default")
      (node (ref "P3") (pin "1") (pinfunction "1_1") (pintype "unspecified"))
    )
    (net (code "84") (name "unconnected-(P3-Pad2)") (class "Default")
      (node (ref "P3") (pin "2") (pinfunction "2_2") (pintype "unspecified"))
    )
    (net (code "85") (name "unconnected-(P3-Pad3)") (class "Default")
      (node (ref "P3") (pin "3") (pinfunction "3_3") (pintype "unspecified"))
    )
    (net (code "86") (name "unconnected-(P3-Pad4)") (class "Default")
      (node (ref "P3") (pin "4") (pinfunction "4_4") (pintype "unspecified"))
    )
    (net (code "87") (name "unconnected-(P3-Pad5)") (class "Default")
      (node (ref "P3") (pin "5") (pinfunction "5_5") (pintype "unspecified"))
    )
    (net (code "88") (name "unconnected-(U1-PA9-Pad42)") (class "Default")
      (node (ref "U1") (pin "42") (pinfunction "PA9_42") (pintype "unspecified+no_connect"))
    )
    (net (code "89") (name "unconnected-(U1-PA15-Pad50)") (class "Default")
      (node (ref "U1") (pin "50") (pinfunction "PA15_50") (pintype "unspecified+no_connect"))
    )
    (net (code "90") (name "unconnected-(U1-PB3-Pad55)") (class "Default")
      (node (ref "U1") (pin "55") (pinfunction "PB3_55") (pintype "unspecified+no_connect"))
    )
    (net (code "91") (name "unconnected-(U1-PB4-Pad56)") (class "Default")
      (node (ref "U1") (pin "56") (pinfunction "PB4_56") (pintype "unspecified+no_connect"))
    )
    (net (code "92") (name "unconnected-(U1-PB5-Pad57)") (class "Default")
      (node (ref "U1") (pin "57") (pinfunction "PB5_57") (pintype "unspecified+no_connect"))
    )
    (net (code "93") (name "unconnected-(U1-PB6-Pad58)") (class "Default")
      (node (ref "U1") (pin "58") (pinfunction "PB6_58") (pintype "unspecified+no_connect"))
    )
    (net (code "94") (name "unconnected-(U1-PB9-Pad62)") (class "Default")
      (node (ref "U1") (pin "62") (pinfunction "PB9_62") (pintype "unspecified+no_connect"))
    )
    (net (code "95") (name "unconnected-(U1-PC4-Pad24)") (class "Default")
      (node (ref "U1") (pin "24") (pinfunction "PC4_24") (pintype "unspecified+no_connect"))
    )
    (net (code "96") (name "unconnected-(U1-PC11-Pad52)") (class "Default")
      (node (ref "U1") (pin "52") (pinfunction "PC11_52") (pintype "unspecified+no_connect"))
    )
    (net (code "97") (name "unconnected-(U1-PC14{slash}OSC32_IN-Pad3)") (class "Default")
      (node (ref "U1") (pin "3") (pinfunction "PC14/OSC32_IN_3") (pintype "unspecified+no_connect"))
    )
    (net (code "98") (name "unconnected-(U1-PC15{slash}OSC32_OUT-Pad4)") (class "Default")
      (node (ref "U1") (pin "4") (pinfunction "PC15/OSC32_OUT_4") (pintype "unspecified+no_connect"))
    )
    (net (code "99") (name "unconnected-(U1-PD2-Pad54)") (class "Default")
      (node (ref "U1") (pin "54") (pinfunction "PD2_54") (pintype "unspecified+no_connect"))
    )
  )
)
